# power_extension.net
KiCad netlist of a schematic drawn in EAGLE
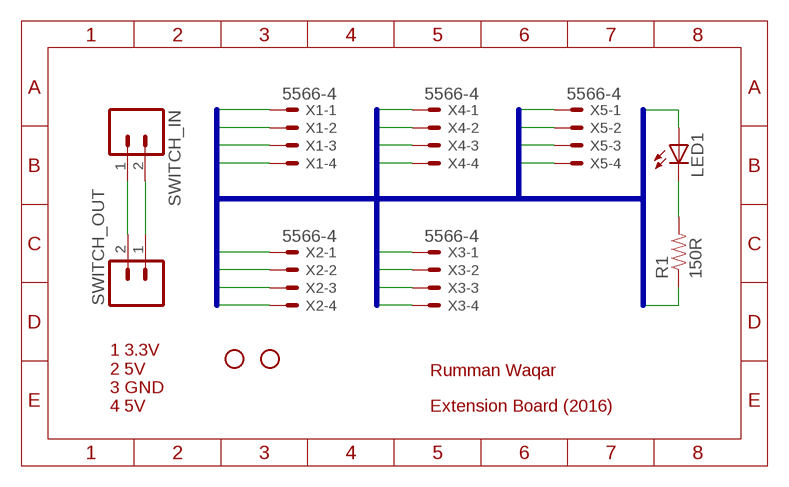
[diagram p0: schematic, sheet 1]

(export (version "E")
  (design (tool "Eeschema 10.0.6"))
  (components
    (comp (ref "JP1")
      (value "STAND-OFF")
      (footprint "eagle-import:STAND-OFF")
      (libsource (lib "eagle-import") (part "STAND-OFF"))
    )
    (comp (ref "JP2")
      (value "STAND-OFF")
      (footprint "eagle-import:STAND-OFF")
      (libsource (lib "eagle-import") (part "STAND-OFF"))
    )
    (comp (ref "LED1")
      (value "LED-FKIT-1206")
      (footprint "eagle-import:FKIT-LED-1206")
      (libsource (lib "eagle-import") (part "LED-FKIT-1206"))
    )
    (comp (ref "R1")
      (value "150R")
      (footprint "eagle-import:0805")
      (libsource (lib "eagle-import") (part "RESISTOR0805-RES"))
    )
    (comp (ref "SWITCH_IN")
      (value "M02POLAR")
      (footprint "eagle-import:MOLEX-1X2")
      (libsource (lib "eagle-import") (part "M02POLAR"))
    )
    (comp (ref "SWITCH_OUT")
      (value "M02POLAR")
      (footprint "eagle-import:MOLEX-1X2")
      (libsource (lib "eagle-import") (part "M02POLAR"))
    )
    (comp (ref "X1")
      (value "5566-4")
      (footprint "eagle-import:5566-4")
      (libsource (lib "eagle-import") (part "5566-4"))
    )
    (comp (ref "X2")
      (value "5566-4")
      (footprint "eagle-import:5566-4")
      (libsource (lib "eagle-import") (part "5566-4"))
    )
    (comp (ref "X3")
      (value "5566-4")
      (footprint "eagle-import:5566-4")
      (libsource (lib "eagle-import") (part "5566-4"))
    )
    (comp (ref "X4")
      (value "5566-4")
      (footprint "eagle-import:5566-4")
      (libsource (lib "eagle-import") (part "5566-4"))
    )
    (comp (ref "X5")
      (value "5566-4")
      (footprint "eagle-import:5566-4")
      (libsource (lib "eagle-import") (part "5566-4"))
    )
  )
  (nets
    (net (code "1") (name "/P1") (class "Default")
      (node (ref "X1") (pin "1") (pinfunction "S_1") (pintype "passive"))
      (node (ref "X2") (pin "1") (pinfunction "S_1") (pintype "passive"))
      (node (ref "X3") (pin "1") (pinfunction "S_1") (pintype "passive"))
      (node (ref "X4") (pin "1") (pinfunction "S_1") (pintype "passive"))
      (node (ref "X5") (pin "1") (pinfunction "S_1") (pintype "passive"))
    )
    (net (code "2") (name "/P2") (class "Default")
      (node (ref "X1") (pin "2") (pinfunction "S_2") (pintype "passive"))
      (node (ref "X2") (pin "2") (pinfunction "S_2") (pintype "passive"))
      (node (ref "X3") (pin "2") (pinfunction "S_2") (pintype "passive"))
      (node (ref "X4") (pin "2") (pinfunction "S_2") (pintype "passive"))
      (node (ref "X5") (pin "2") (pinfunction "S_2") (pintype "passive"))
    )
    (net (code "3") (name "/P3") (class "Default")
      (node (ref "R1") (pin "1") (pinfunction "1_1") (pintype "passive"))
      (node (ref "X1") (pin "3") (pinfunction "S_3") (pintype "passive"))
      (node (ref "X2") (pin "3") (pinfunction "S_3") (pintype "passive"))
      (node (ref "X3") (pin "3") (pinfunction "S_3") (pintype "passive"))
      (node (ref "X4") (pin "3") (pinfunction "S_3") (pintype "passive"))
      (node (ref "X5") (pin "3") (pinfunction "S_3") (pintype "passive"))
    )
    (net (code "4") (name "/P4") (class "Default")
      (node (ref "LED1") (pin "A") (pinfunction "A_A") (pintype "passive"))
      (node (ref "X1") (pin "4") (pinfunction "S_4") (pintype "passive"))
      (node (ref "X2") (pin "4") (pinfunction "S_4") (pintype "passive"))
      (node (ref "X3") (pin "4") (pinfunction "S_4") (pintype "passive"))
      (node (ref "X4") (pin "4") (pinfunction "S_4") (pintype "passive"))
      (node (ref "X5") (pin "4") (pinfunction "S_4") (pintype "passive"))
    )
    (net (code "5") (name "Net-(LED1-PadC)") (class "Default")
      (node (ref "LED1") (pin "C") (pinfunction "C_C") (pintype "passive"))
      (node (ref "R1") (pin "2") (pinfunction "2_2") (pintype "passive"))
    )
    (net (code "6") (name "Net-(SWITCH_IN-Pad1)") (class "Default")
      (node (ref "SWITCH_IN") (pin "1") (pinfunction "1_1") (pintype "passive"))
      (node (ref "SWITCH_OUT") (pin "2") (pinfunction "2_2") (pintype "passive"))
    )
    (net (code "7") (name "Net-(SWITCH_IN-Pad2)") (class "Default")
      (node (ref "SWITCH_IN") (pin "2") (pinfunction "2_2") (pintype "passive"))
      (node (ref "SWITCH_OUT") (pin "1") (pinfunction "1_1") (pintype "passive"))
    )
  )
)
